# Sheet1.net
KiCad netlist of a schematic drawn in Altium Designer
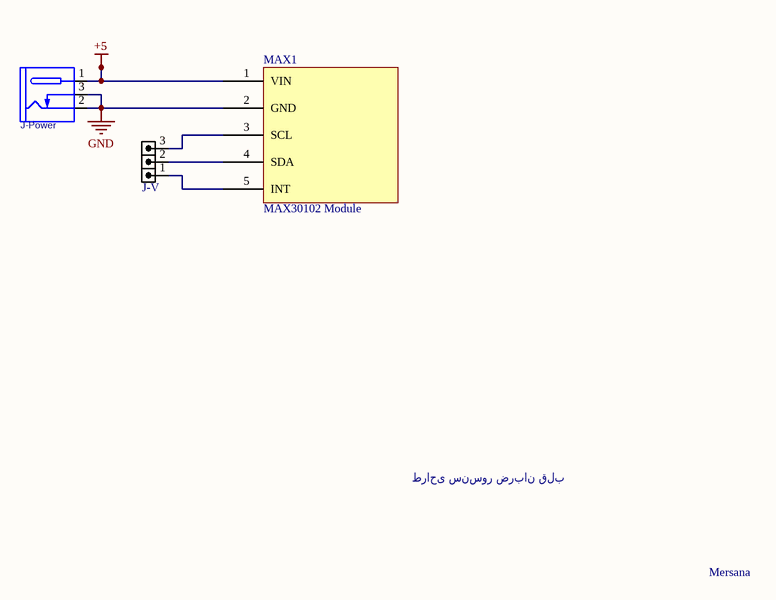
[diagram p0: Sheet1.SchDoc]

(export (version "E")
  (design (tool "Eeschema 10.0.6"))
  (components
    (comp (ref "J-Power")
      (value "DC_POWER_JACK")
      (footprint "JAC_PWR2")
      (description "CONN, PWR JACK DC, PLUG DIAM 2.0MM RA THD")
      (fields
        (field (name "MANF") "CUI STACK")
        (field (name "MANF_P#") "PJ-202A, PJ-002AH, PJ-102AH, KLDX-0202")
      )
      (libsource (lib "conn_powerJack") (part "CONN_PWR_JACKR2"))
    )
    (comp (ref "J-V")
      (value "HDRM3")
      (footprint "HDR_M_1X3")
      (description "CONN, HEADER, Male, pitch: 2.54mm, 3POS")
      (libsource (lib "conn_header_2.54mm_st") (part "HDR_M_1X3"))
    )
    (comp (ref "MAX1")
      (value "MAX30102 Module")
      (footprint "MAX30102-MODULE")
      (description "MAX30102, Heart Rate Module")
      (libsource (lib "Schlib1") (part "MODULE-MAX30102"))
    )
  )
  (nets
    (net (code "1") (name "+5") (class "Default")
      (node (ref "J-Power") (pin "1") (pinfunction "TIP_1") (pintype "power_in"))
      (node (ref "MAX1") (pin "1") (pinfunction "VIN_1") (pintype "passive"))
    )
    (net (code "2") (name "GND") (class "Default")
      (node (ref "J-Power") (pin "2") (pinfunction "SLEEVE_2") (pintype "power_in"))
      (node (ref "J-Power") (pin "3") (pinfunction "INSERTION_DET_3") (pintype "power_in"))
      (node (ref "MAX1") (pin "2") (pinfunction "GND_2") (pintype "passive"))
    )
    (net (code "3") (name "Net-(MAX1-INT)") (class "Default")
      (node (ref "J-V") (pin "1") (pinfunction "1_1") (pintype "passive"))
      (node (ref "MAX1") (pin "5") (pinfunction "INT_5") (pintype "passive"))
    )
    (net (code "4") (name "Net-(MAX1-SCL)") (class "Default")
      (node (ref "J-V") (pin "3") (pinfunction "3_3") (pintype "passive"))
      (node (ref "MAX1") (pin "3") (pinfunction "SCL_3") (pintype "passive"))
    )
    (net (code "5") (name "Net-(MAX1-SDA)") (class "Default")
      (node (ref "J-V") (pin "2") (pinfunction "2_2") (pintype "passive"))
      (node (ref "MAX1") (pin "4") (pinfunction "SDA_4") (pintype "passive"))
    )
  )
)
